# Power_Sheet.net
KiCad netlist of a schematic drawn in Altium Designer
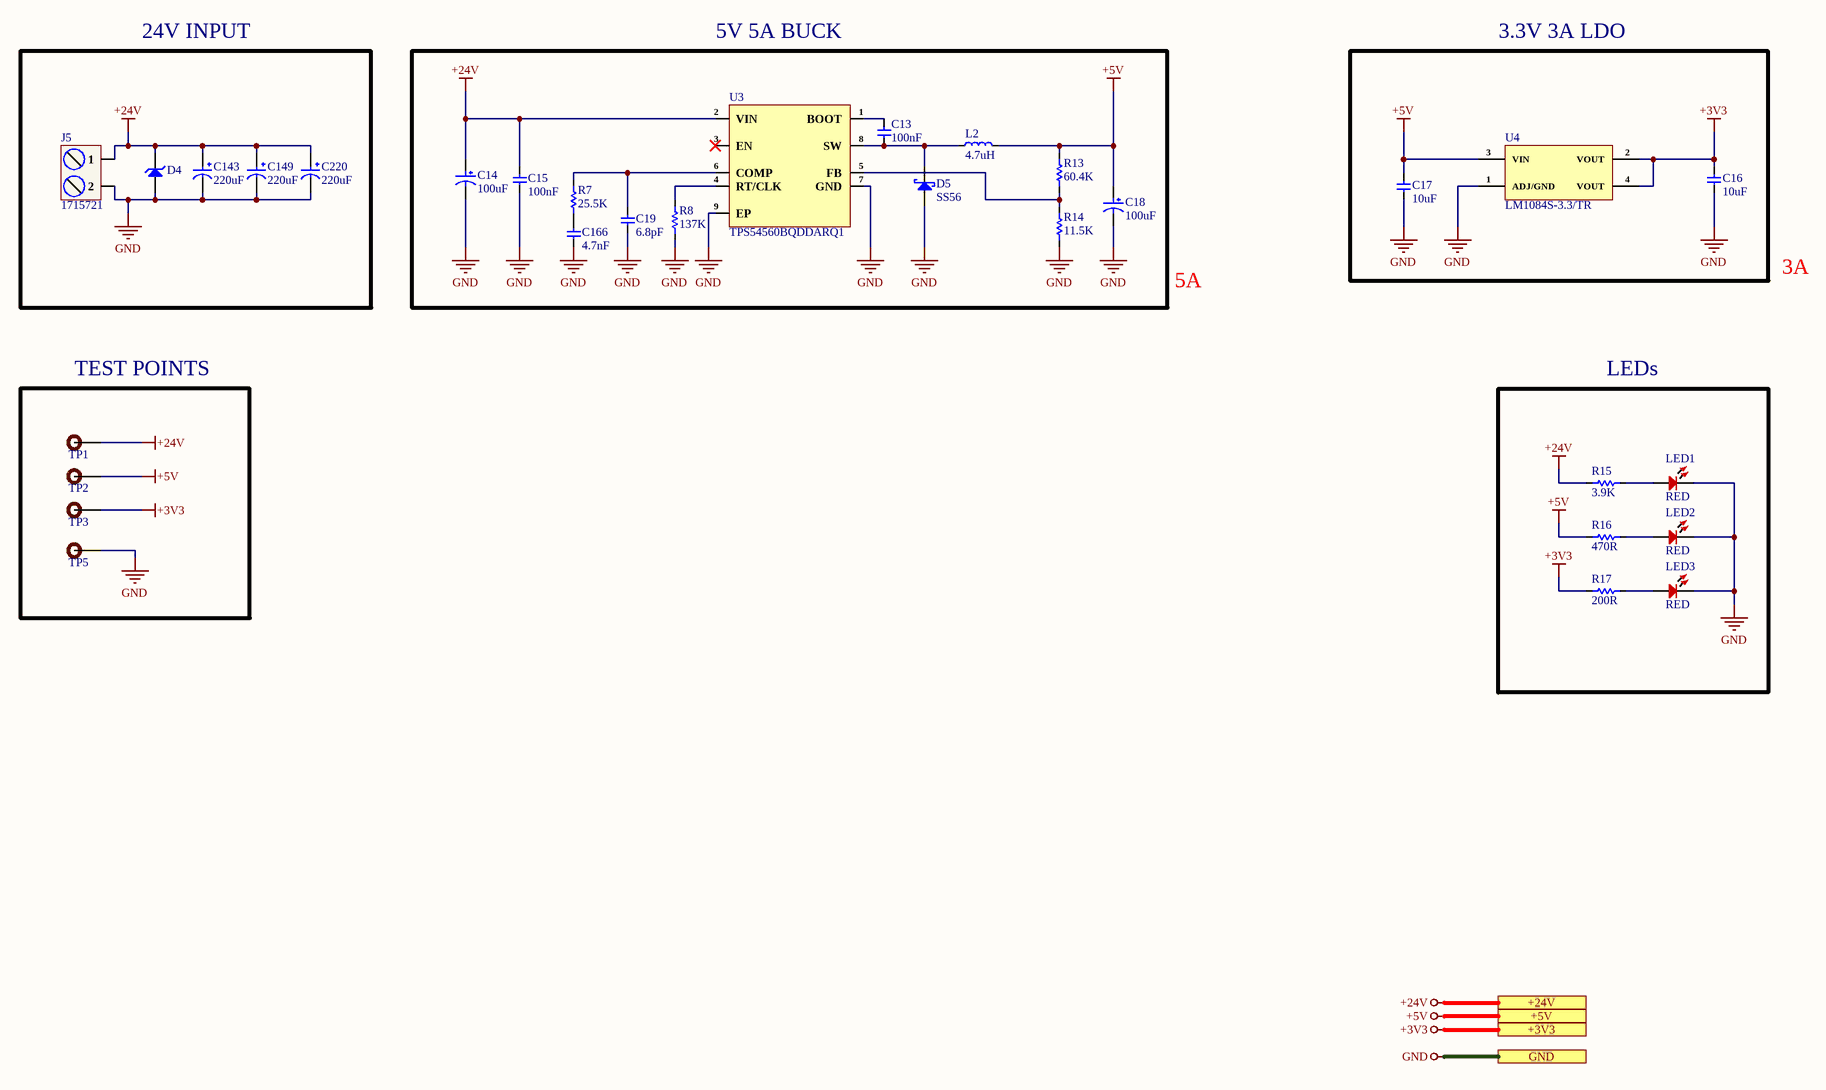
[diagram p0: Power_Sheet.SchDoc]

(export (version "E")
  (design (tool "Eeschema 10.0.6"))
  (components
    (comp (ref "C13")
      (value "100nF")
      (footprint "cap-0402")
      (description "CAP CER 0.1UF 50V X7R 0402")
      (fields
        (field (name "MANUFACTURER") "TDK")
        (field (name "MANUFACTURER PART NUMBER") "C1005X7R1H104KT000F")
      )
      (libsource (lib "eSpark Libraries") (part "C1005X7R1H104KT000F"))
    )
    (comp (ref "C14")
      (value "100uF")
      (footprint "RVT1A101M0605")
      (description "100uF 10V 55mA@120Hz ±20% SMD,D6.3xL5.4mm Aluminum Electrolytic Capacitors - SMD ROHS")
      (fields
        (field (name "MANUFACTURER") "ROQANG")
        (field (name "MANUFACTURER PART NUMBER") "RVT1A101M0605")
      )
      (libsource (lib "eSpark Libraries") (part "RVT1A101M0605"))
    )
    (comp (ref "C15")
      (value "100nF")
      (footprint "cap-0402")
      (description "CAP CER 0.1UF 50V X7R 0402")
      (fields
        (field (name "MANUFACTURER") "TDK")
        (field (name "MANUFACTURER PART NUMBER") "C1005X7R1H104KT000F")
      )
      (libsource (lib "eSpark Libraries") (part "C1005X7R1H104KT000F"))
    )
    (comp (ref "C16")
      (value "10uF")
      (footprint "Cap-0603")
      (description "CAP CER 10UF 25V X5R 0603")
      (fields
        (field (name "MANUFACTURER") "TDK")
        (field (name "MANUFACTURER PART NUMBER") "C1608X5R1E106M080AC")
      )
      (libsource (lib "eSpark Libraries") (part "C1608X5R1E106M080AC"))
    )
    (comp (ref "C17")
      (value "10uF")
      (footprint "Cap-0603")
      (description "CAP CER 10UF 25V X5R 0603")
      (fields
        (field (name "MANUFACTURER") "TDK")
        (field (name "MANUFACTURER PART NUMBER") "C1608X5R1E106M080AC")
      )
      (libsource (lib "eSpark Libraries") (part "C1608X5R1E106M080AC"))
    )
    (comp (ref "C18")
      (value "100uF")
      (footprint "RVT1A101M0605")
      (description "100uF 10V 55mA@120Hz ±20% SMD,D6.3xL5.4mm Aluminum Electrolytic Capacitors - SMD ROHS")
      (fields
        (field (name "MANUFACTURER") "ROQANG")
        (field (name "MANUFACTURER PART NUMBER") "RVT1A101M0605")
      )
      (libsource (lib "eSpark Libraries") (part "RVT1A101M0605"))
    )
    (comp (ref "C19")
      (value "6.8pF")
      (footprint "Cap-0402")
      (description "CAP CER 6.8PF 50V C0G/NPO 0402")
      (fields
        (field (name "MANUFACTURER") "Yageo")
        (field (name "MANUFACTURER PART NUMBER") "CC0402CRNPO9BN6R8")
      )
      (libsource (lib "eSpark Libraries") (part "CC0402CRNPO9BN6R8"))
    )
    (comp (ref "C143")
      (value "220uF")
      (footprint "UCD-220uF-10mmDia")
      (description "CAP ALUM 220UF 20% 50V SMD")
      (fields
        (field (name "MANUFACTURER") "Nichicon")
        (field (name "MANUFACTURER PART NUMBER") "UCD1H221MNL1GS")
      )
      (libsource (lib "eSpark Libraries") (part "UCD1H221MNL1GS"))
    )
    (comp (ref "C149")
      (value "220uF")
      (footprint "UCD-220uF-10mmDia")
      (description "CAP ALUM 220UF 20% 50V SMD")
      (fields
        (field (name "MANUFACTURER") "Nichicon")
        (field (name "MANUFACTURER PART NUMBER") "UCD1H221MNL1GS")
      )
      (libsource (lib "eSpark Libraries") (part "UCD1H221MNL1GS"))
    )
    (comp (ref "C166")
      (value "4.7nF")
      (footprint "Cap-0402")
      (description "CAP CER 4700PF 50V X7R 0402")
      (fields
        (field (name "MANUFACTURER") "Yageo")
        (field (name "MANUFACTURER PART NUMBER") "CC0402KRX7R9BB472")
      )
      (libsource (lib "eSpark Libraries") (part "CC0402KRX7R9BB472"))
    )
    (comp (ref "C220")
      (value "220uF")
      (footprint "UCD-220uF-10mmDia")
      (description "CAP ALUM 220UF 20% 50V SMD")
      (fields
        (field (name "MANUFACTURER") "Nichicon")
        (field (name "MANUFACTURER PART NUMBER") "UCD1H221MNL1GS")
      )
      (libsource (lib "eSpark Libraries") (part "UCD1H221MNL1GS"))
    )
    (comp (ref "D4")
      (value "SMBJ28A-13-F")
      (footprint "SMB_")
      (description "TVS DIODE 28VWM 45.4VC SMB")
      (fields (field (name "MANUFACTURER") "Diodes"))
      (libsource (lib "eSpark Libraries") (part "SMBJ28A-13-F"))
    )
    (comp (ref "D5")
      (value "SS56")
      (footprint "SMA")
      (description "DIODE SCHOTTKY 60V 5A SMA")
      (fields (field (name "MANUFACTURER") "MDD"))
      (libsource (lib "eSpark Libraries") (part "SS56"))
    )
    (comp (ref "J5")
      (value "1715721")
      (footprint "1715721")
      (description "TERM BLK 2P SIDE ENT 5.08MM PCB")
      (fields (field (name "MANUFACTURER") "Phoenix Contact"))
      (libsource (lib "eSpark Libraries") (part "1715721"))
    )
    (comp (ref "L2")
      (value "4.7uH")
      (footprint "YSPI1050-4R7M")
      (description "8A 4.7uH ±20% SMD,10x10.1mm Power Inductors ROHS")
      (fields
        (field (name "MANUFACTURER") "YJYCOIN")
        (field (name "MANUFACTURER PART NUMBER") "YSPI1050-4R7M")
      )
      (libsource (lib "eSpark Libraries") (part "YSPI1050-4R7M"))
    )
    (comp (ref "LED1")
      (value "RED")
      (footprint "LED-0603")
      (description "RED LED 0603 Light Emitting Diodes")
      (fields
        (field (name "MANUFACTURER") "Foshan NationStar Optoelectronics")
        (field (name "MANUFACTURER PART NUMBER") "NCD0603R3")
      )
      (libsource (lib "eSpark Libraries") (part "NCD0603R3"))
    )
    (comp (ref "LED2")
      (value "RED")
      (footprint "LED-0603")
      (description "RED LED 0603 Light Emitting Diodes")
      (fields
        (field (name "MANUFACTURER") "Foshan NationStar Optoelectronics")
        (field (name "MANUFACTURER PART NUMBER") "NCD0603R3")
      )
      (libsource (lib "eSpark Libraries") (part "NCD0603R3"))
    )
    (comp (ref "LED3")
      (value "RED")
      (footprint "LED-0603")
      (description "RED LED 0603 Light Emitting Diodes")
      (fields
        (field (name "MANUFACTURER") "Foshan NationStar Optoelectronics")
        (field (name "MANUFACTURER PART NUMBER") "NCD0603R3")
      )
      (libsource (lib "eSpark Libraries") (part "NCD0603R3"))
    )
    (comp (ref "R7")
      (value "25.5K")
      (footprint "Res-0402")
      (description "62.5mW Thick Film Resistors 50V ±100ppm/℃ ±1% 25.5kΩ 0402 Chip Resistor - Surface Mount ROHS")
      (fields
        (field (name "LCSC PART NUMBER") "C26970")
        (field (name "MANUFACTURER") "Royal Electronic Factory")
      )
      (libsource (lib "eSpark Libraries") (part "0402WGF2552TCE"))
    )
    (comp (ref "R8")
      (value "137K")
      (footprint "Res-0402")
      (description "RES SMD 137K OHM 0.1% 1/16W 0402")
      (fields (field (name "LCSC PART NUMBER") "C852519") (field (name "MANUFACTURER") "Yageo"))
      (libsource (lib "eSpark Libraries") (part "RT0402BRD07137KL"))
    )
    (comp (ref "R13")
      (value "60.4K")
      (footprint "Res-0402")
      (description "60.4kΩ 50V 62.5mW Thick Film Resistors ±1% 0402 Chip Resistor - Surface Mount ROHS")
      (fields (field (name "MANUFACTURER") "VO") (field (name "MANUFACTURER PART NUMBER") "SCR0402F60K4"))
      (libsource (lib "eSpark Libraries") (part "SCR0402F60K4"))
    )
    (comp (ref "R14")
      (value "11.5K")
      (footprint "Res-0402")
      (description "11.5kΩ 50V 62.5mW Thick Film Resistors ±100ppm/℃ ±1%  0402 Chip Resistor - Surface Mount ROHS")
      (fields
        (field (name "MANUFACTURER") "FOJAN")
        (field (name "MANUFACTURER PART NUMBER") "FRC0402F1152TS")
      )
      (libsource (lib "eSpark Libraries") (part "FRC0402F1152TS"))
    )
    (comp (ref "R15")
      (value "3.9K")
      (footprint "Res-0402")
      (description "RES 3.9K OHM 1% 1/16W 0402")
      (fields
        (field (name "MANUFACTURER") "Yageo")
        (field (name "MANUFACTURER PART NUMBER") "RC0402FR-073K9L")
      )
      (libsource (lib "eSpark Libraries") (part "RC0402FR-073K9L"))
    )
    (comp (ref "R16")
      (value "470R")
      (footprint "Res-0402")
      (description "RES 470 OHM 1% 1/16W 0402")
      (fields
        (field (name "MANUFACTURER") "Yageo")
        (field (name "MANUFACTURER PART NUMBER") "RC0402FR-07470RL")
      )
      (libsource (lib "eSpark Libraries") (part "RC0402FR-07470RL"))
    )
    (comp (ref "R17")
      (value "200R")
      (footprint "Res-0402")
      (description "RES 200 OHM 1% 1/16W 0402")
      (fields
        (field (name "MANUFACTURER") "Yageo")
        (field (name "MANUFACTURER PART NUMBER") "RC0402FR-07200RL")
      )
      (libsource (lib "eSpark Libraries") (part "RC0402FR-07200RL"))
    )
    (comp (ref "TP1")
      (value "TEST POINT")
      (footprint "Test-point")
      (description "Test Point ON")
      (libsource (lib "eSpark Libraries") (part "TEST POINT"))
    )
    (comp (ref "TP2")
      (value "TEST POINT")
      (footprint "Test-point")
      (description "Test Point ON")
      (libsource (lib "eSpark Libraries") (part "TEST POINT"))
    )
    (comp (ref "TP3")
      (value "TEST POINT")
      (footprint "Test-point")
      (description "Test Point ON")
      (libsource (lib "eSpark Libraries") (part "TEST POINT"))
    )
    (comp (ref "TP5")
      (value "TEST POINT")
      (footprint "Test-point")
      (description "Test Point ON")
      (libsource (lib "eSpark Libraries") (part "TEST POINT"))
    )
    (comp (ref "U3")
      (value "TPS54560BQDDARQ1")
      (footprint "8-SO PowerPad")
      (description "IC REG BCK SPLIT RAIL ADJ 8SOPWR")
      (fields (field (name "MANUFACTURER") "Texas Instruments") (field (name "LCSC PART NUMBER") "C2072188"))
      (libsource (lib "eSpark Libraries") (part "TPS54560BQDDARQ1"))
    )
    (comp (ref "U4")
      (value "LM1084S-3.3/TR")
      (footprint "TO263-3_")
      (description "72dB@(120Hz) 5A Fixed 3.3V~3.3V Positive 12V TO-263-3 Linear Voltage Regulators (LDO) ROHS")
      (fields (field (name "MANUFACTURER") "HGSEMI") (field (name "LCSC PART NUMBER") "C259972"))
      (libsource (lib "eSpark Libraries") (part "LM1084S-3.3/TR"))
    )
  )
  (nets
    (net (code "1") (name "+3V3") (class "Default")
      (node (ref "C16") (pin "2") (pinfunction "2_2") (pintype "passive"))
      (node (ref "R17") (pin "1") (pinfunction "1_1") (pintype "passive"))
      (node (ref "TP3") (pin "1") (pinfunction "1_1") (pintype "passive"))
      (node (ref "U4") (pin "2") (pinfunction "VOUT_2") (pintype "passive"))
      (node (ref "U4") (pin "4") (pinfunction "VOUT_4") (pintype "passive"))
    )
    (net (code "2") (name "+5V") (class "Default")
      (node (ref "C17") (pin "2") (pinfunction "2_2") (pintype "passive"))
      (node (ref "C18") (pin "1") (pintype "passive"))
      (node (ref "L2") (pin "2") (pinfunction "2_2") (pintype "passive"))
      (node (ref "R13") (pin "2") (pinfunction "2_2") (pintype "passive"))
      (node (ref "R16") (pin "1") (pinfunction "1_1") (pintype "passive"))
      (node (ref "TP2") (pin "1") (pinfunction "1_1") (pintype "passive"))
      (node (ref "U4") (pin "3") (pinfunction "VIN_3") (pintype "passive"))
    )
    (net (code "3") (name "+24V") (class "Default")
      (node (ref "C14") (pin "1") (pintype "passive"))
      (node (ref "C143") (pin "1") (pinfunction "1_1") (pintype "passive"))
      (node (ref "C149") (pin "1") (pinfunction "1_1") (pintype "passive"))
      (node (ref "C15") (pin "2") (pinfunction "2_2") (pintype "passive"))
      (node (ref "C220") (pin "1") (pinfunction "1_1") (pintype "passive"))
      (node (ref "D4") (pin "2") (pinfunction "K_2") (pintype "passive"))
      (node (ref "J5") (pin "1") (pinfunction "1_1") (pintype "passive"))
      (node (ref "R15") (pin "1") (pinfunction "1_1") (pintype "passive"))
      (node (ref "TP1") (pin "1") (pinfunction "1_1") (pintype "passive"))
      (node (ref "U3") (pin "2") (pinfunction "VIN_2") (pintype "passive"))
    )
    (net (code "4") (name "GND") (class "Default")
      (node (ref "C14") (pin "2") (pintype "passive"))
      (node (ref "C143") (pin "2") (pinfunction "2_2") (pintype "passive"))
      (node (ref "C149") (pin "2") (pinfunction "2_2") (pintype "passive"))
      (node (ref "C15") (pin "1") (pinfunction "1_1") (pintype "passive"))
      (node (ref "C16") (pin "1") (pinfunction "1_1") (pintype "passive"))
      (node (ref "C166") (pin "1") (pinfunction "1_1") (pintype "passive"))
      (node (ref "C17") (pin "1") (pinfunction "1_1") (pintype "passive"))
      (node (ref "C18") (pin "2") (pintype "passive"))
      (node (ref "C19") (pin "1") (pinfunction "1_1") (pintype "passive"))
      (node (ref "C220") (pin "2") (pinfunction "2_2") (pintype "passive"))
      (node (ref "D4") (pin "1") (pinfunction "A_1") (pintype "passive"))
      (node (ref "D5") (pin "2") (pinfunction "A_2") (pintype "passive"))
      (node (ref "J5") (pin "2") (pinfunction "2_2") (pintype "passive"))
      (node (ref "LED1") (pin "2") (pinfunction "2_2") (pintype "passive"))
      (node (ref "LED2") (pin "2") (pinfunction "2_2") (pintype "passive"))
      (node (ref "LED3") (pin "2") (pinfunction "2_2") (pintype "passive"))
      (node (ref "R14") (pin "1") (pinfunction "1_1") (pintype "passive"))
      (node (ref "R8") (pin "1") (pinfunction "1_1") (pintype "passive"))
      (node (ref "TP5") (pin "1") (pinfunction "1_1") (pintype "passive"))
      (node (ref "U3") (pin "7") (pinfunction "GND_7") (pintype "passive"))
      (node (ref "U3") (pin "9") (pinfunction "EP_9") (pintype "passive"))
      (node (ref "U4") (pin "1") (pinfunction "ADJ/GND_1") (pintype "passive"))
    )
    (net (code "5") (name "Net-(C166-Pad2)") (class "Default")
      (node (ref "C166") (pin "2") (pinfunction "2_2") (pintype "passive"))
      (node (ref "R7") (pin "1") (pinfunction "1_1") (pintype "passive"))
    )
    (net (code "6") (name "Net-(D5-K)") (class "Default")
      (node (ref "C13") (pin "1") (pinfunction "1_1") (pintype "passive"))
      (node (ref "D5") (pin "1") (pinfunction "K_1") (pintype "passive"))
      (node (ref "L2") (pin "1") (pinfunction "1_1") (pintype "passive"))
      (node (ref "U3") (pin "8") (pinfunction "SW_8") (pintype "passive"))
    )
    (net (code "7") (name "Net-(LED1-Pad1)") (class "Default")
      (node (ref "LED1") (pin "1") (pinfunction "1_1") (pintype "passive"))
      (node (ref "R15") (pin "2") (pinfunction "2_2") (pintype "passive"))
    )
    (net (code "8") (name "Net-(LED2-Pad1)") (class "Default")
      (node (ref "LED2") (pin "1") (pinfunction "1_1") (pintype "passive"))
      (node (ref "R16") (pin "2") (pinfunction "2_2") (pintype "passive"))
    )
    (net (code "9") (name "Net-(LED3-Pad1)") (class "Default")
      (node (ref "LED3") (pin "1") (pinfunction "1_1") (pintype "passive"))
      (node (ref "R17") (pin "2") (pinfunction "2_2") (pintype "passive"))
    )
    (net (code "10") (name "Net-(U3-BOOT)") (class "Default")
      (node (ref "C13") (pin "2") (pinfunction "2_2") (pintype "passive"))
      (node (ref "U3") (pin "1") (pinfunction "BOOT_1") (pintype "passive"))
    )
    (net (code "11") (name "Net-(U3-COMP)") (class "Default")
      (node (ref "C19") (pin "2") (pinfunction "2_2") (pintype "passive"))
      (node (ref "R7") (pin "2") (pinfunction "2_2") (pintype "passive"))
      (node (ref "U3") (pin "6") (pinfunction "COMP_6") (pintype "passive"))
    )
    (net (code "12") (name "Net-(U3-FB)") (class "Default")
      (node (ref "R13") (pin "1") (pinfunction "1_1") (pintype "passive"))
      (node (ref "R14") (pin "2") (pinfunction "2_2") (pintype "passive"))
      (node (ref "U3") (pin "5") (pinfunction "FB_5") (pintype "passive"))
    )
    (net (code "13") (name "Net-(U3-RT{slash}CLK)") (class "Default")
      (node (ref "R8") (pin "2") (pinfunction "2_2") (pintype "passive"))
      (node (ref "U3") (pin "4") (pinfunction "RT/CLK_4") (pintype "passive"))
    )
    (net (code "14") (name "unconnected-(U3-EN-Pad3)") (class "Default")
      (node (ref "U3") (pin "3") (pinfunction "EN_3") (pintype "passive+no_connect"))
    )
  )
)
